# CPUBoard.net
KiCad netlist of a schematic drawn in EAGLE
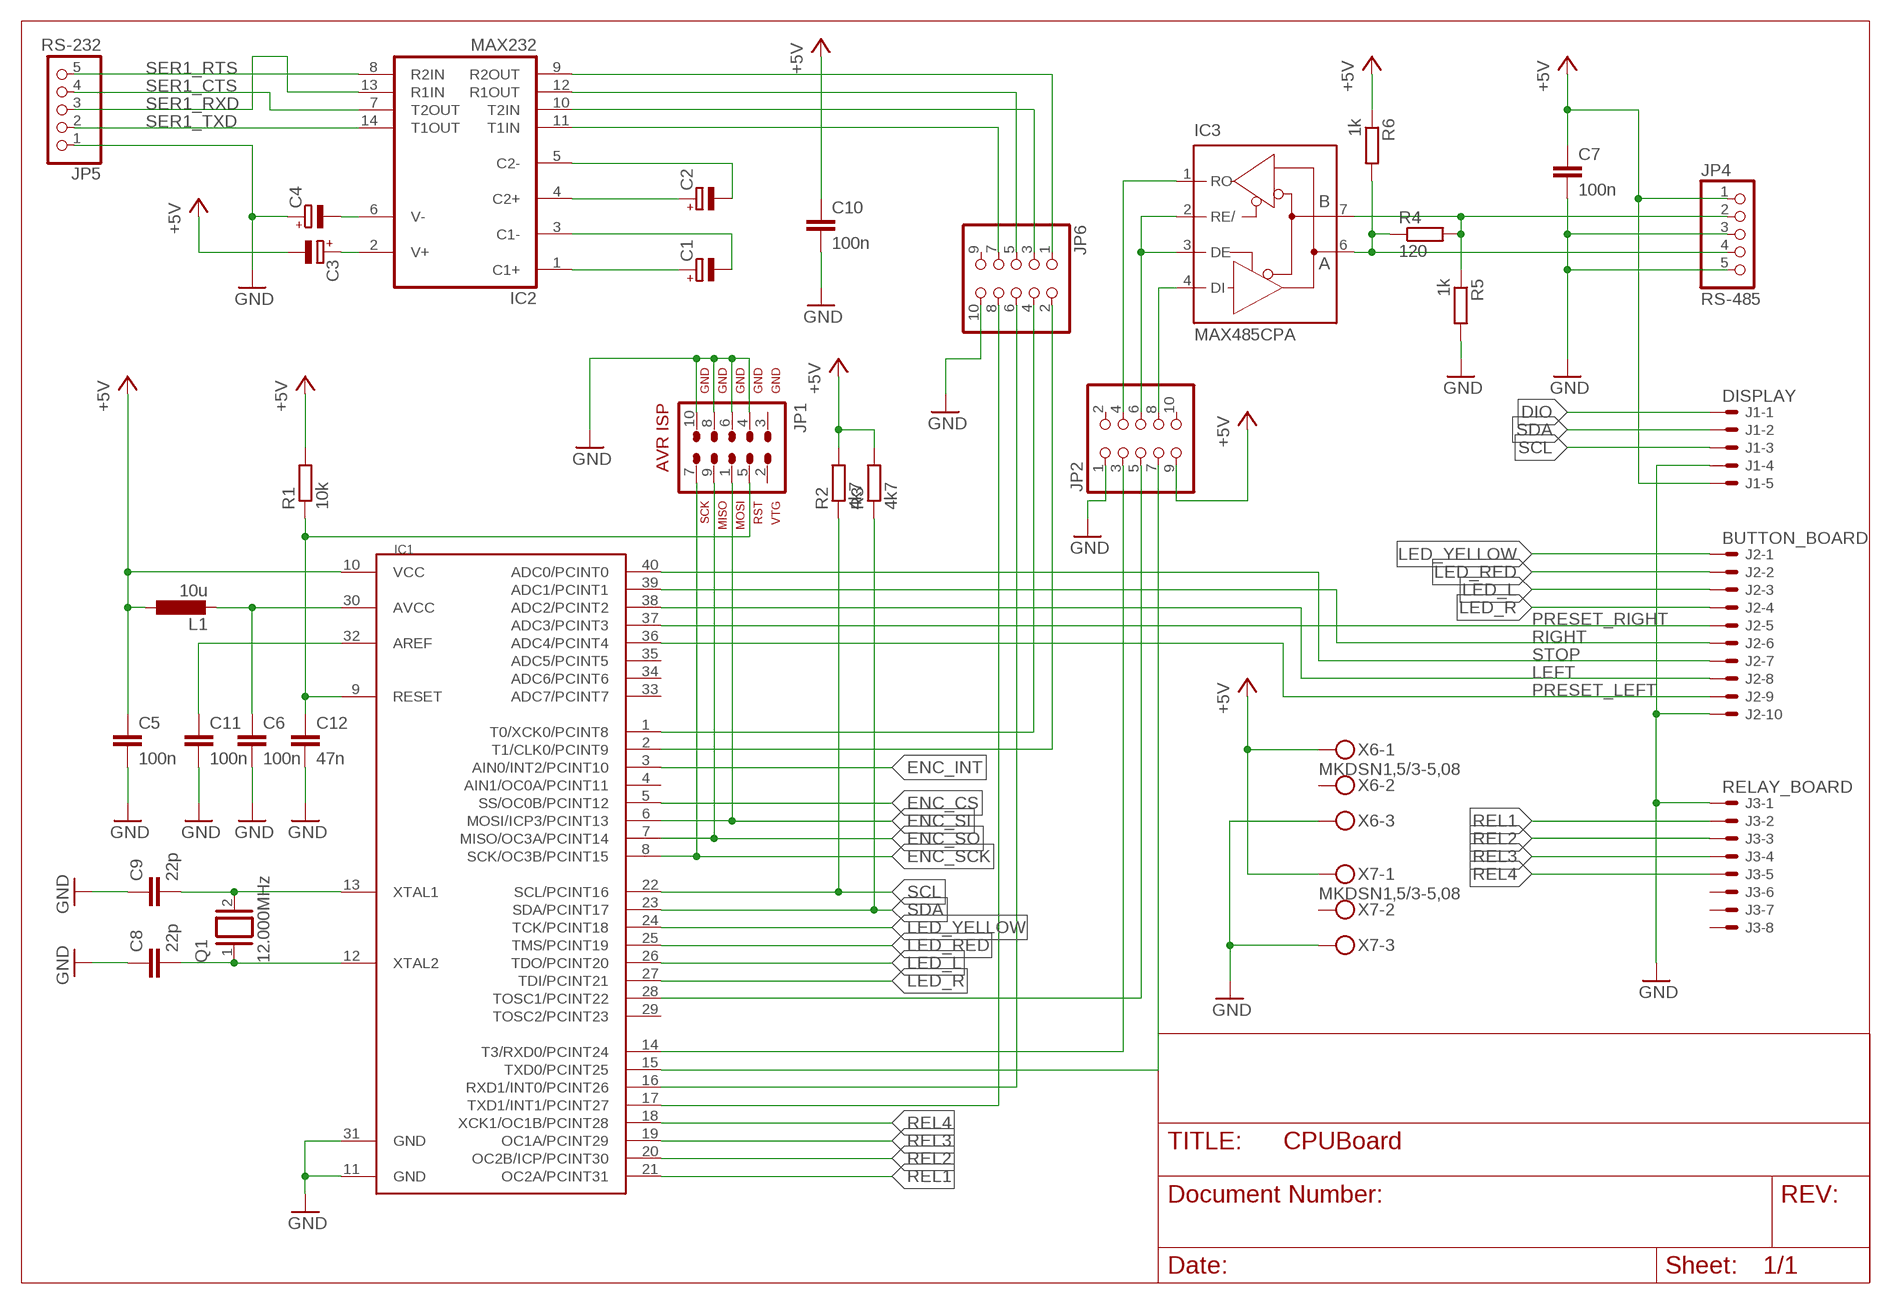
[diagram p0: schematic, sheet 1]

(export (version "E")
  (design (tool "Eeschema 10.0.6"))
  (components
    (comp (ref "C1")
      (value "CPOL-EUE2,5-6E")
      (footprint "eagle-import:E2,5-6E")
      (libsource (lib "eagle-import") (part "CPOL-EUE2,5-6E"))
    )
    (comp (ref "C2")
      (value "CPOL-EUE2,5-6E")
      (footprint "eagle-import:E2,5-6E")
      (libsource (lib "eagle-import") (part "CPOL-EUE2,5-6E"))
    )
    (comp (ref "C3")
      (value "CPOL-EUE2,5-6E")
      (footprint "eagle-import:E2,5-6E")
      (libsource (lib "eagle-import") (part "CPOL-EUE2,5-6E"))
    )
    (comp (ref "C4")
      (value "CPOL-EUE2,5-6E")
      (footprint "eagle-import:E2,5-6E")
      (libsource (lib "eagle-import") (part "CPOL-EUE2,5-6E"))
    )
    (comp (ref "C5")
      (value "100n")
      (footprint "eagle-import:C025-025X050")
      (libsource (lib "eagle-import") (part "C-EU025-025X050"))
    )
    (comp (ref "C6")
      (value "100n")
      (footprint "eagle-import:C025-025X050")
      (libsource (lib "eagle-import") (part "C-EU025-025X050"))
    )
    (comp (ref "C7")
      (value "100n")
      (footprint "eagle-import:C025-025X050")
      (libsource (lib "eagle-import") (part "C-EU025-025X050"))
    )
    (comp (ref "C8")
      (value "22p")
      (footprint "eagle-import:C025-024X044")
      (libsource (lib "eagle-import") (part "resistor_C-EU025-024X044"))
    )
    (comp (ref "C9")
      (value "22p")
      (footprint "eagle-import:C025-024X044")
      (libsource (lib "eagle-import") (part "resistor_C-EU025-024X044"))
    )
    (comp (ref "C10")
      (value "100n")
      (footprint "eagle-import:C025-025X050")
      (libsource (lib "eagle-import") (part "C-EU025-025X050"))
    )
    (comp (ref "C11")
      (value "100n")
      (footprint "eagle-import:C025-025X050")
      (libsource (lib "eagle-import") (part "C-EU025-025X050"))
    )
    (comp (ref "C12")
      (value "47n")
      (footprint "eagle-import:C025-025X050")
      (libsource (lib "eagle-import") (part "C-EU025-025X050"))
    )
    (comp (ref "IC1")
      (value "MEGA1284P")
      (footprint "eagle-import:DIL40")
      (libsource (lib "eagle-import") (part "MEGA1284P"))
    )
    (comp (ref "IC2")
      (value "MAX232")
      (footprint "eagle-import:DIL16")
      (fields (field (name "MF") "MAXIM") (field (name "MPN") "MAX232ACPE+"))
      (libsource (lib "eagle-import") (part "MAX232"))
    )
    (comp (ref "IC3")
      (value "MAX485CPA")
      (footprint "eagle-import:DIL08")
      (fields (field (name "MPN") "MAX481CPA+"))
      (libsource (lib "eagle-import") (part "MAX481CPA"))
    )
    (comp (ref "J1")
      (value "DISPLAY")
      (footprint "eagle-import:6410-05")
      (libsource (lib "eagle-import") (part "22-?-0527-2051"))
    )
    (comp (ref "J2")
      (value "BUTTON_BOARD")
      (footprint "eagle-import:6410-10")
      (libsource (lib "eagle-import") (part "22-?-1027-2101"))
    )
    (comp (ref "J3")
      (value "RELAY_BOARD")
      (footprint "eagle-import:6410-08")
      (libsource (lib "eagle-import") (part "22-?-0827-2081"))
    )
    (comp (ref "JP1")
      (value "AVR-ISP-10")
      (footprint "eagle-import:AVR-ISP-10")
      (libsource (lib "eagle-import") (part "AVR-ISP-10"))
    )
    (comp (ref "JP2")
      (value "PINHD-2X5")
      (footprint "eagle-import:2X05")
      (libsource (lib "eagle-import") (part "PINHD-2X5"))
    )
    (comp (ref "JP4")
      (value "RS-485")
      (footprint "eagle-import:1X05")
      (libsource (lib "eagle-import") (part "PINHD-1X5"))
    )
    (comp (ref "JP5")
      (value "RS-232")
      (footprint "eagle-import:1X05")
      (libsource (lib "eagle-import") (part "PINHD-1X5"))
    )
    (comp (ref "JP6")
      (value "PINHD-2X5")
      (footprint "eagle-import:2X05")
      (libsource (lib "eagle-import") (part "PINHD-2X5"))
    )
    (comp (ref "L1")
      (value "10u")
      (footprint "eagle-import:0207_10")
      (libsource (lib "eagle-import") (part "L-EU0207/10"))
    )
    (comp (ref "Q1")
      (value "12.000MHz")
      (footprint "eagle-import:QS")
      (libsource (lib "eagle-import") (part "XTAL/S"))
    )
    (comp (ref "R1")
      (value "10k")
      (footprint "eagle-import:0207_10")
      (libsource (lib "eagle-import") (part "R-EU_0207/10"))
    )
    (comp (ref "R2")
      (value "4k7")
      (footprint "eagle-import:0207_10")
      (libsource (lib "eagle-import") (part "R-EU_0207/10"))
    )
    (comp (ref "R3")
      (value "4k7")
      (footprint "eagle-import:0207_10")
      (libsource (lib "eagle-import") (part "R-EU_0207/10"))
    )
    (comp (ref "R4")
      (value "120")
      (footprint "eagle-import:0207_10")
      (libsource (lib "eagle-import") (part "R-EU_0207/10"))
    )
    (comp (ref "R5")
      (value "1k")
      (footprint "eagle-import:0207_10")
      (libsource (lib "eagle-import") (part "R-EU_0207/10"))
    )
    (comp (ref "R6")
      (value "1k")
      (footprint "eagle-import:0207_10")
      (libsource (lib "eagle-import") (part "R-EU_0207/10"))
    )
    (comp (ref "X6")
      (value "MKDSN1,5/3-5,08")
      (footprint "eagle-import:MKDSN1,5_3-5,08")
      (fields (field (name "MPN") "SMKDSN1,5/3-5,08"))
      (libsource (lib "eagle-import") (part "MKDSN1,5/3-5,08"))
    )
    (comp (ref "X7")
      (value "MKDSN1,5/3-5,08")
      (footprint "eagle-import:MKDSN1,5_3-5,08")
      (fields (field (name "MPN") "SMKDSN1,5/3-5,08"))
      (libsource (lib "eagle-import") (part "MKDSN1,5/3-5,08"))
    )
  )
  (nets
    (net (code "1") (name "+5V") (class "Default")
      (node (ref "C10") (pin "1") (pinfunction "1_1") (pintype "passive"))
      (node (ref "C3") (pin "-") (pinfunction "-_-") (pintype "passive"))
      (node (ref "C5") (pin "1") (pinfunction "1_1") (pintype "passive"))
      (node (ref "C7") (pin "1") (pinfunction "1_1") (pintype "passive"))
      (node (ref "IC1") (pin "10") (pinfunction "VCC_10") (pintype "bidirectional"))
      (node (ref "J1") (pin "5") (pinfunction "S_5") (pintype "passive"))
      (node (ref "JP2") (pin "9") (pinfunction "9_9") (pintype "passive"))
      (node (ref "JP4") (pin "1") (pinfunction "1_1") (pintype "passive"))
      (node (ref "L1") (pin "1") (pinfunction "1_1") (pintype "passive"))
      (node (ref "R1") (pin "2") (pinfunction "2_2") (pintype "passive"))
      (node (ref "R2") (pin "2") (pinfunction "2_2") (pintype "passive"))
      (node (ref "R3") (pin "2") (pinfunction "2_2") (pintype "passive"))
      (node (ref "R6") (pin "1") (pinfunction "1_1") (pintype "passive"))
      (node (ref "X6") (pin "1") (pinfunction "KL_1") (pintype "passive"))
      (node (ref "X7") (pin "1") (pinfunction "KL_1") (pintype "passive"))
    )
    (net (code "2") (name "/LEFT") (class "Default")
      (node (ref "IC1") (pin "38") (pinfunction "ADC2/PCINT2_38") (pintype "bidirectional"))
      (node (ref "J2") (pin "8") (pinfunction "S_8") (pintype "passive"))
    )
    (net (code "3") (name "/PRESET_LEFT") (class "Default")
      (node (ref "IC1") (pin "36") (pinfunction "ADC4/PCINT4_36") (pintype "bidirectional"))
      (node (ref "J2") (pin "9") (pinfunction "S_9") (pintype "passive"))
    )
    (net (code "4") (name "/PRESET_RIGHT") (class "Default")
      (node (ref "IC1") (pin "37") (pinfunction "ADC3/PCINT3_37") (pintype "bidirectional"))
      (node (ref "J2") (pin "5") (pinfunction "S_5") (pintype "passive"))
    )
    (net (code "5") (name "/RIGHT") (class "Default")
      (node (ref "IC1") (pin "39") (pinfunction "ADC1/PCINT1_39") (pintype "bidirectional"))
      (node (ref "J2") (pin "6") (pinfunction "S_6") (pintype "passive"))
    )
    (net (code "6") (name "/SER1_CTS") (class "Default")
      (node (ref "IC2") (pin "13") (pinfunction "R1IN_13") (pintype "input"))
      (node (ref "JP5") (pin "3") (pinfunction "3_3") (pintype "passive"))
    )
    (net (code "7") (name "/SER1_RTS") (class "Default")
      (node (ref "IC2") (pin "8") (pinfunction "R2IN_8") (pintype "input"))
      (node (ref "JP5") (pin "5") (pinfunction "5_5") (pintype "passive"))
    )
    (net (code "8") (name "/SER1_RXD") (class "Default")
      (node (ref "IC2") (pin "7") (pinfunction "T2OUT_7") (pintype "output"))
      (node (ref "JP5") (pin "4") (pinfunction "4_4") (pintype "passive"))
    )
    (net (code "9") (name "/SER1_TXD") (class "Default")
      (node (ref "IC2") (pin "14") (pinfunction "T1OUT_14") (pintype "output"))
      (node (ref "JP5") (pin "2") (pinfunction "2_2") (pintype "passive"))
    )
    (net (code "10") (name "/STOP") (class "Default")
      (node (ref "IC1") (pin "40") (pinfunction "ADC0/PCINT0_40") (pintype "bidirectional"))
      (node (ref "J2") (pin "7") (pinfunction "S_7") (pintype "passive"))
    )
    (net (code "11") (name "DIO") (class "Default")
      (node (ref "J1") (pin "1") (pinfunction "S_1") (pintype "passive"))
    )
    (net (code "12") (name "ENC_CS") (class "Default")
      (node (ref "IC1") (pin "5") (pinfunction "SS/OC0B/PCINT12_5") (pintype "bidirectional"))
    )
    (net (code "13") (name "ENC_INT") (class "Default")
      (node (ref "IC1") (pin "3") (pinfunction "AIN0/INT2/PCINT10_3") (pintype "bidirectional"))
    )
    (net (code "14") (name "ENC_SCK") (class "Default")
      (node (ref "IC1") (pin "8") (pinfunction "SCK/OC3B/PCINT15_8") (pintype "bidirectional"))
      (node (ref "JP1") (pin "7") (pinfunction "7_7") (pintype "passive"))
    )
    (net (code "15") (name "ENC_SI") (class "Default")
      (node (ref "IC1") (pin "6") (pinfunction "MOSI/ICP3/PCINT13_6") (pintype "bidirectional"))
      (node (ref "JP1") (pin "1") (pinfunction "1_1") (pintype "passive"))
    )
    (net (code "16") (name "ENC_SO") (class "Default")
      (node (ref "IC1") (pin "7") (pinfunction "MISO/OC3A/PCINT14_7") (pintype "bidirectional"))
      (node (ref "JP1") (pin "9") (pinfunction "9_9") (pintype "passive"))
    )
    (net (code "17") (name "GND") (class "Default")
      (node (ref "C10") (pin "2") (pinfunction "2_2") (pintype "passive"))
      (node (ref "C11") (pin "2") (pinfunction "2_2") (pintype "passive"))
      (node (ref "C12") (pin "2") (pinfunction "2_2") (pintype "passive"))
      (node (ref "C4") (pin "+") (pinfunction "+_+") (pintype "passive"))
      (node (ref "C5") (pin "2") (pinfunction "2_2") (pintype "passive"))
      (node (ref "C6") (pin "2") (pinfunction "2_2") (pintype "passive"))
      (node (ref "C7") (pin "2") (pinfunction "2_2") (pintype "passive"))
      (node (ref "C8") (pin "1") (pinfunction "1_1") (pintype "passive"))
      (node (ref "C9") (pin "1") (pinfunction "1_1") (pintype "passive"))
      (node (ref "IC1") (pin "11") (pinfunction "GND_11") (pintype "bidirectional"))
      (node (ref "IC1") (pin "31") (pinfunction "GND_31") (pintype "bidirectional"))
      (node (ref "J1") (pin "4") (pinfunction "S_4") (pintype "passive"))
      (node (ref "J2") (pin "10") (pinfunction "S_10") (pintype "passive"))
      (node (ref "J3") (pin "1") (pinfunction "S_1") (pintype "passive"))
      (node (ref "JP1") (pin "10") (pinfunction "10_10") (pintype "passive"))
      (node (ref "JP1") (pin "4") (pinfunction "4_4") (pintype "passive"))
      (node (ref "JP1") (pin "6") (pinfunction "6_6") (pintype "passive"))
      (node (ref "JP1") (pin "8") (pinfunction "8_8") (pintype "passive"))
      (node (ref "JP2") (pin "1") (pinfunction "1_1") (pintype "passive"))
      (node (ref "JP4") (pin "3") (pinfunction "3_3") (pintype "passive"))
      (node (ref "JP4") (pin "5") (pinfunction "5_5") (pintype "passive"))
      (node (ref "JP5") (pin "1") (pinfunction "1_1") (pintype "passive"))
      (node (ref "JP6") (pin "10") (pinfunction "10_10") (pintype "passive"))
      (node (ref "R5") (pin "2") (pinfunction "2_2") (pintype "passive"))
      (node (ref "X6") (pin "3") (pinfunction "KL_3") (pintype "passive"))
      (node (ref "X7") (pin "3") (pinfunction "KL_3") (pintype "passive"))
    )
    (net (code "18") (name "LED_L") (class "Default")
      (node (ref "IC1") (pin "26") (pinfunction "TDO/PCINT20_26") (pintype "bidirectional"))
      (node (ref "J2") (pin "3") (pinfunction "S_3") (pintype "passive"))
    )
    (net (code "19") (name "LED_R") (class "Default")
      (node (ref "IC1") (pin "27") (pinfunction "TDI/PCINT21_27") (pintype "bidirectional"))
      (node (ref "J2") (pin "4") (pinfunction "S_4") (pintype "passive"))
    )
    (net (code "20") (name "LED_RED") (class "Default")
      (node (ref "IC1") (pin "25") (pinfunction "TMS/PCINT19_25") (pintype "bidirectional"))
      (node (ref "J2") (pin "2") (pinfunction "S_2") (pintype "passive"))
    )
    (net (code "21") (name "LED_YELLOW") (class "Default")
      (node (ref "IC1") (pin "24") (pinfunction "TCK/PCINT18_24") (pintype "bidirectional"))
      (node (ref "J2") (pin "1") (pinfunction "S_1") (pintype "passive"))
    )
    (net (code "22") (name "Net-(IC1-AREF)") (class "Default")
      (node (ref "C11") (pin "1") (pinfunction "1_1") (pintype "passive"))
      (node (ref "IC1") (pin "32") (pinfunction "AREF_32") (pintype "bidirectional"))
    )
    (net (code "23") (name "Net-(IC1-AVCC)") (class "Default")
      (node (ref "C6") (pin "1") (pinfunction "1_1") (pintype "passive"))
      (node (ref "IC1") (pin "30") (pinfunction "AVCC_30") (pintype "bidirectional"))
      (node (ref "L1") (pin "2") (pinfunction "2_2") (pintype "passive"))
    )
    (net (code "24") (name "Net-(IC1-RESET)") (class "Default")
      (node (ref "C12") (pin "1") (pinfunction "1_1") (pintype "passive"))
      (node (ref "IC1") (pin "9") (pinfunction "RESET_9") (pintype "bidirectional"))
      (node (ref "JP1") (pin "5") (pinfunction "5_5") (pintype "passive"))
      (node (ref "R1") (pin "1") (pinfunction "1_1") (pintype "passive"))
    )
    (net (code "25") (name "Net-(IC1-RXD1{slash}INT0{slash}PCINT26)") (class "Default")
      (node (ref "IC1") (pin "16") (pinfunction "RXD1/INT0/PCINT26_16") (pintype "bidirectional"))
      (node (ref "JP6") (pin "6") (pinfunction "6_6") (pintype "passive"))
    )
    (net (code "26") (name "Net-(IC1-T0{slash}XCK0{slash}PCINT8)") (class "Default")
      (node (ref "IC1") (pin "1") (pinfunction "T0/XCK0/PCINT8_1") (pintype "bidirectional"))
      (node (ref "JP6") (pin "4") (pinfunction "4_4") (pintype "passive"))
    )
    (net (code "27") (name "Net-(IC1-T1{slash}CLK0{slash}PCINT9)") (class "Default")
      (node (ref "IC1") (pin "2") (pinfunction "T1/CLK0/PCINT9_2") (pintype "bidirectional"))
      (node (ref "JP6") (pin "2") (pinfunction "2_2") (pintype "passive"))
    )
    (net (code "28") (name "Net-(IC1-T3{slash}RXD0{slash}PCINT24)") (class "Default")
      (node (ref "IC1") (pin "14") (pinfunction "T3/RXD0/PCINT24_14") (pintype "bidirectional"))
      (node (ref "JP2") (pin "3") (pinfunction "3_3") (pintype "passive"))
    )
    (net (code "29") (name "Net-(IC1-TOSC1{slash}PCINT22)") (class "Default")
      (node (ref "IC1") (pin "28") (pinfunction "TOSC1/PCINT22_28") (pintype "bidirectional"))
      (node (ref "JP2") (pin "5") (pinfunction "5_5") (pintype "passive"))
    )
    (net (code "30") (name "Net-(IC1-TXD0{slash}PCINT25)") (class "Default")
      (node (ref "IC1") (pin "15") (pinfunction "TXD0/PCINT25_15") (pintype "bidirectional"))
      (node (ref "JP2") (pin "7") (pinfunction "7_7") (pintype "passive"))
    )
    (net (code "31") (name "Net-(IC1-TXD1{slash}INT1{slash}PCINT27)") (class "Default")
      (node (ref "IC1") (pin "17") (pinfunction "TXD1/INT1/PCINT27_17") (pintype "bidirectional"))
      (node (ref "JP6") (pin "8") (pinfunction "8_8") (pintype "passive"))
    )
    (net (code "32") (name "Net-(IC1-XTAL1)") (class "Default")
      (node (ref "C9") (pin "2") (pinfunction "2_2") (pintype "passive"))
      (node (ref "IC1") (pin "13") (pinfunction "XTAL1_13") (pintype "bidirectional"))
      (node (ref "Q1") (pin "2") (pinfunction "2_2") (pintype "passive"))
    )
    (net (code "33") (name "Net-(IC1-XTAL2)") (class "Default")
      (node (ref "C8") (pin "2") (pinfunction "2_2") (pintype "passive"))
      (node (ref "IC1") (pin "12") (pinfunction "XTAL2_12") (pintype "bidirectional"))
      (node (ref "Q1") (pin "1") (pinfunction "1_1") (pintype "passive"))
    )
    (net (code "34") (name "Net-(IC2A-C1+)") (class "Default")
      (node (ref "C1") (pin "+") (pinfunction "+_+") (pintype "passive"))
      (node (ref "IC2") (pin "1") (pinfunction "C1+_1") (pintype "bidirectional"))
    )
    (net (code "35") (name "Net-(IC2A-C1-)") (class "Default")
      (node (ref "C1") (pin "-") (pinfunction "-_-") (pintype "passive"))
      (node (ref "IC2") (pin "3") (pinfunction "C1-_3") (pintype "bidirectional"))
    )
    (net (code "36") (name "Net-(IC2A-C2+)") (class "Default")
      (node (ref "C2") (pin "+") (pinfunction "+_+") (pintype "passive"))
      (node (ref "IC2") (pin "4") (pinfunction "C2+_4") (pintype "bidirectional"))
    )
    (net (code "37") (name "Net-(IC2A-C2-)") (class "Default")
      (node (ref "C2") (pin "-") (pinfunction "-_-") (pintype "passive"))
      (node (ref "IC2") (pin "5") (pinfunction "C2-_5") (pintype "bidirectional"))
    )
    (net (code "38") (name "Net-(IC2A-R1OUT)") (class "Default")
      (node (ref "IC2") (pin "12") (pinfunction "R1OUT_12") (pintype "output"))
      (node (ref "JP6") (pin "5") (pinfunction "5_5") (pintype "passive"))
    )
    (net (code "39") (name "Net-(IC2A-R2OUT)") (class "Default")
      (node (ref "IC2") (pin "9") (pinfunction "R2OUT_9") (pintype "output"))
      (node (ref "JP6") (pin "1") (pinfunction "1_1") (pintype "passive"))
    )
    (net (code "40") (name "Net-(IC2A-T1IN)") (class "Default")
      (node (ref "IC2") (pin "11") (pinfunction "T1IN_11") (pintype "input"))
      (node (ref "JP6") (pin "7") (pinfunction "7_7") (pintype "passive"))
    )
    (net (code "41") (name "Net-(IC2A-T2IN)") (class "Default")
      (node (ref "IC2") (pin "10") (pinfunction "T2IN_10") (pintype "input"))
      (node (ref "JP6") (pin "3") (pinfunction "3_3") (pintype "passive"))
    )
    (net (code "42") (name "Net-(IC2A-V+)") (class "Default")
      (node (ref "C3") (pin "+") (pinfunction "+_+") (pintype "passive"))
      (node (ref "IC2") (pin "2") (pinfunction "V+_2") (pintype "bidirectional"))
    )
    (net (code "43") (name "Net-(IC2A-V-)") (class "Default")
      (node (ref "C4") (pin "-") (pinfunction "-_-") (pintype "passive"))
      (node (ref "IC2") (pin "6") (pinfunction "V-_6") (pintype "bidirectional"))
    )
    (net (code "44") (name "Net-(IC3A-A)") (class "Default")
      (node (ref "IC3") (pin "6") (pinfunction "A_6") (pintype "passive"))
      (node (ref "JP4") (pin "4") (pinfunction "4_4") (pintype "passive"))
      (node (ref "R4") (pin "1") (pinfunction "1_1") (pintype "passive"))
      (node (ref "R6") (pin "2") (pinfunction "2_2") (pintype "passive"))
    )
    (net (code "45") (name "Net-(IC3A-B)") (class "Default")
      (node (ref "IC3") (pin "7") (pinfunction "B_7") (pintype "passive"))
      (node (ref "JP4") (pin "2") (pinfunction "2_2") (pintype "passive"))
      (node (ref "R4") (pin "2") (pinfunction "2_2") (pintype "passive"))
      (node (ref "R5") (pin "1") (pinfunction "1_1") (pintype "passive"))
    )
    (net (code "46") (name "Net-(IC3A-DE)") (class "Default")
      (node (ref "IC3") (pin "2") (pinfunction "RE/_2") (pintype "input"))
      (node (ref "IC3") (pin "3") (pinfunction "DE_3") (pintype "input"))
      (node (ref "JP2") (pin "6") (pinfunction "6_6") (pintype "passive"))
    )
    (net (code "47") (name "Net-(IC3A-DI)") (class "Default")
      (node (ref "IC3") (pin "4") (pinfunction "DI_4") (pintype "input"))
      (node (ref "JP2") (pin "8") (pinfunction "8_8") (pintype "passive"))
    )
    (net (code "48") (name "Net-(IC3A-RO)") (class "Default")
      (node (ref "IC3") (pin "1") (pinfunction "RO_1") (pintype "output"))
      (node (ref "JP2") (pin "4") (pinfunction "4_4") (pintype "passive"))
    )
    (net (code "49") (name "REL1") (class "Default")
      (node (ref "IC1") (pin "21") (pinfunction "OC2A/PCINT31_21") (pintype "bidirectional"))
      (node (ref "J3") (pin "2") (pinfunction "S_2") (pintype "passive"))
    )
    (net (code "50") (name "REL2") (class "Default")
      (node (ref "IC1") (pin "20") (pinfunction "OC2B/ICP/PCINT30_20") (pintype "bidirectional"))
      (node (ref "J3") (pin "3") (pinfunction "S_3") (pintype "passive"))
    )
    (net (code "51") (name "REL3") (class "Default")
      (node (ref "IC1") (pin "19") (pinfunction "OC1A/PCINT29_19") (pintype "bidirectional"))
      (node (ref "J3") (pin "4") (pinfunction "S_4") (pintype "passive"))
    )
    (net (code "52") (name "REL4") (class "Default")
      (node (ref "IC1") (pin "18") (pinfunction "XCK1/OC1B/PCINT28_18") (pintype "bidirectional"))
      (node (ref "J3") (pin "5") (pinfunction "S_5") (pintype "passive"))
    )
    (net (code "53") (name "SCL") (class "Default")
      (node (ref "IC1") (pin "22") (pinfunction "SCL/PCINT16_22") (pintype "bidirectional"))
      (node (ref "J1") (pin "3") (pinfunction "S_3") (pintype "passive"))
      (node (ref "R2") (pin "1") (pinfunction "1_1") (pintype "passive"))
    )
    (net (code "54") (name "SDA") (class "Default")
      (node (ref "IC1") (pin "23") (pinfunction "SDA/PCINT17_23") (pintype "bidirectional"))
      (node (ref "J1") (pin "2") (pinfunction "S_2") (pintype "passive"))
      (node (ref "R3") (pin "1") (pinfunction "1_1") (pintype "passive"))
    )
    (net (code "55") (name "unconnected-(IC1-ADC5{slash}PCINT5-Pad35)") (class "Default")
      (node (ref "IC1") (pin "35") (pinfunction "ADC5/PCINT5_35") (pintype "bidirectional"))
    )
    (net (code "56") (name "unconnected-(IC1-ADC6{slash}PCINT6-Pad34)") (class "Default")
      (node (ref "IC1") (pin "34") (pinfunction "ADC6/PCINT6_34") (pintype "bidirectional"))
    )
    (net (code "57") (name "unconnected-(IC1-ADC7{slash}PCINT7-Pad33)") (class "Default")
      (node (ref "IC1") (pin "33") (pinfunction "ADC7/PCINT7_33") (pintype "bidirectional"))
    )
    (net (code "58") (name "unconnected-(IC1-AIN1{slash}OC0A{slash}PCINT11-Pad4)") (class "Default")
      (node (ref "IC1") (pin "4") (pinfunction "AIN1/OC0A/PCINT11_4") (pintype "bidirectional"))
    )
    (net (code "59") (name "unconnected-(IC1-TOSC2{slash}PCINT23-Pad29)") (class "Default")
      (node (ref "IC1") (pin "29") (pinfunction "TOSC2/PCINT23_29") (pintype "bidirectional"))
    )
    (net (code "60") (name "unconnected-(J3F-S-Pad6)") (class "Default")
      (node (ref "J3") (pin "6") (pinfunction "S_6") (pintype "passive"))
    )
    (net (code "61") (name "unconnected-(J3G-S-Pad7)") (class "Default")
      (node (ref "J3") (pin "7") (pinfunction "S_7") (pintype "passive"))
    )
    (net (code "62") (name "unconnected-(J3H-S-Pad8)") (class "Default")
      (node (ref "J3") (pin "8") (pinfunction "S_8") (pintype "passive"))
    )
    (net (code "63") (name "unconnected-(JP1-Pad2)") (class "Default")
      (node (ref "JP1") (pin "2") (pinfunction "2_2") (pintype "passive"))
    )
    (net (code "64") (name "unconnected-(JP1-Pad3)") (class "Default")
      (node (ref "JP1") (pin "3") (pinfunction "3_3") (pintype "passive"))
    )
    (net (code "65") (name "unconnected-(JP2-Pad2)") (class "Default")
      (node (ref "JP2") (pin "2") (pinfunction "2_2") (pintype "passive"))
    )
    (net (code "66") (name "unconnected-(JP2-Pad10)") (class "Default")
      (node (ref "JP2") (pin "10") (pinfunction "10_10") (pintype "passive"))
    )
    (net (code "67") (name "unconnected-(JP6-Pad9)") (class "Default")
      (node (ref "JP6") (pin "9") (pinfunction "9_9") (pintype "passive"))
    )
    (net (code "68") (name "unconnected-(X6B-KL-Pad2)") (class "Default")
      (node (ref "X6") (pin "2") (pinfunction "KL_2") (pintype "passive"))
    )
    (net (code "69") (name "unconnected-(X7B-KL-Pad2)") (class "Default")
      (node (ref "X7") (pin "2") (pinfunction "KL_2") (pintype "passive"))
    )
  )
)
